# design.net
KiCad netlist of a schematic drawn in Altium Designer
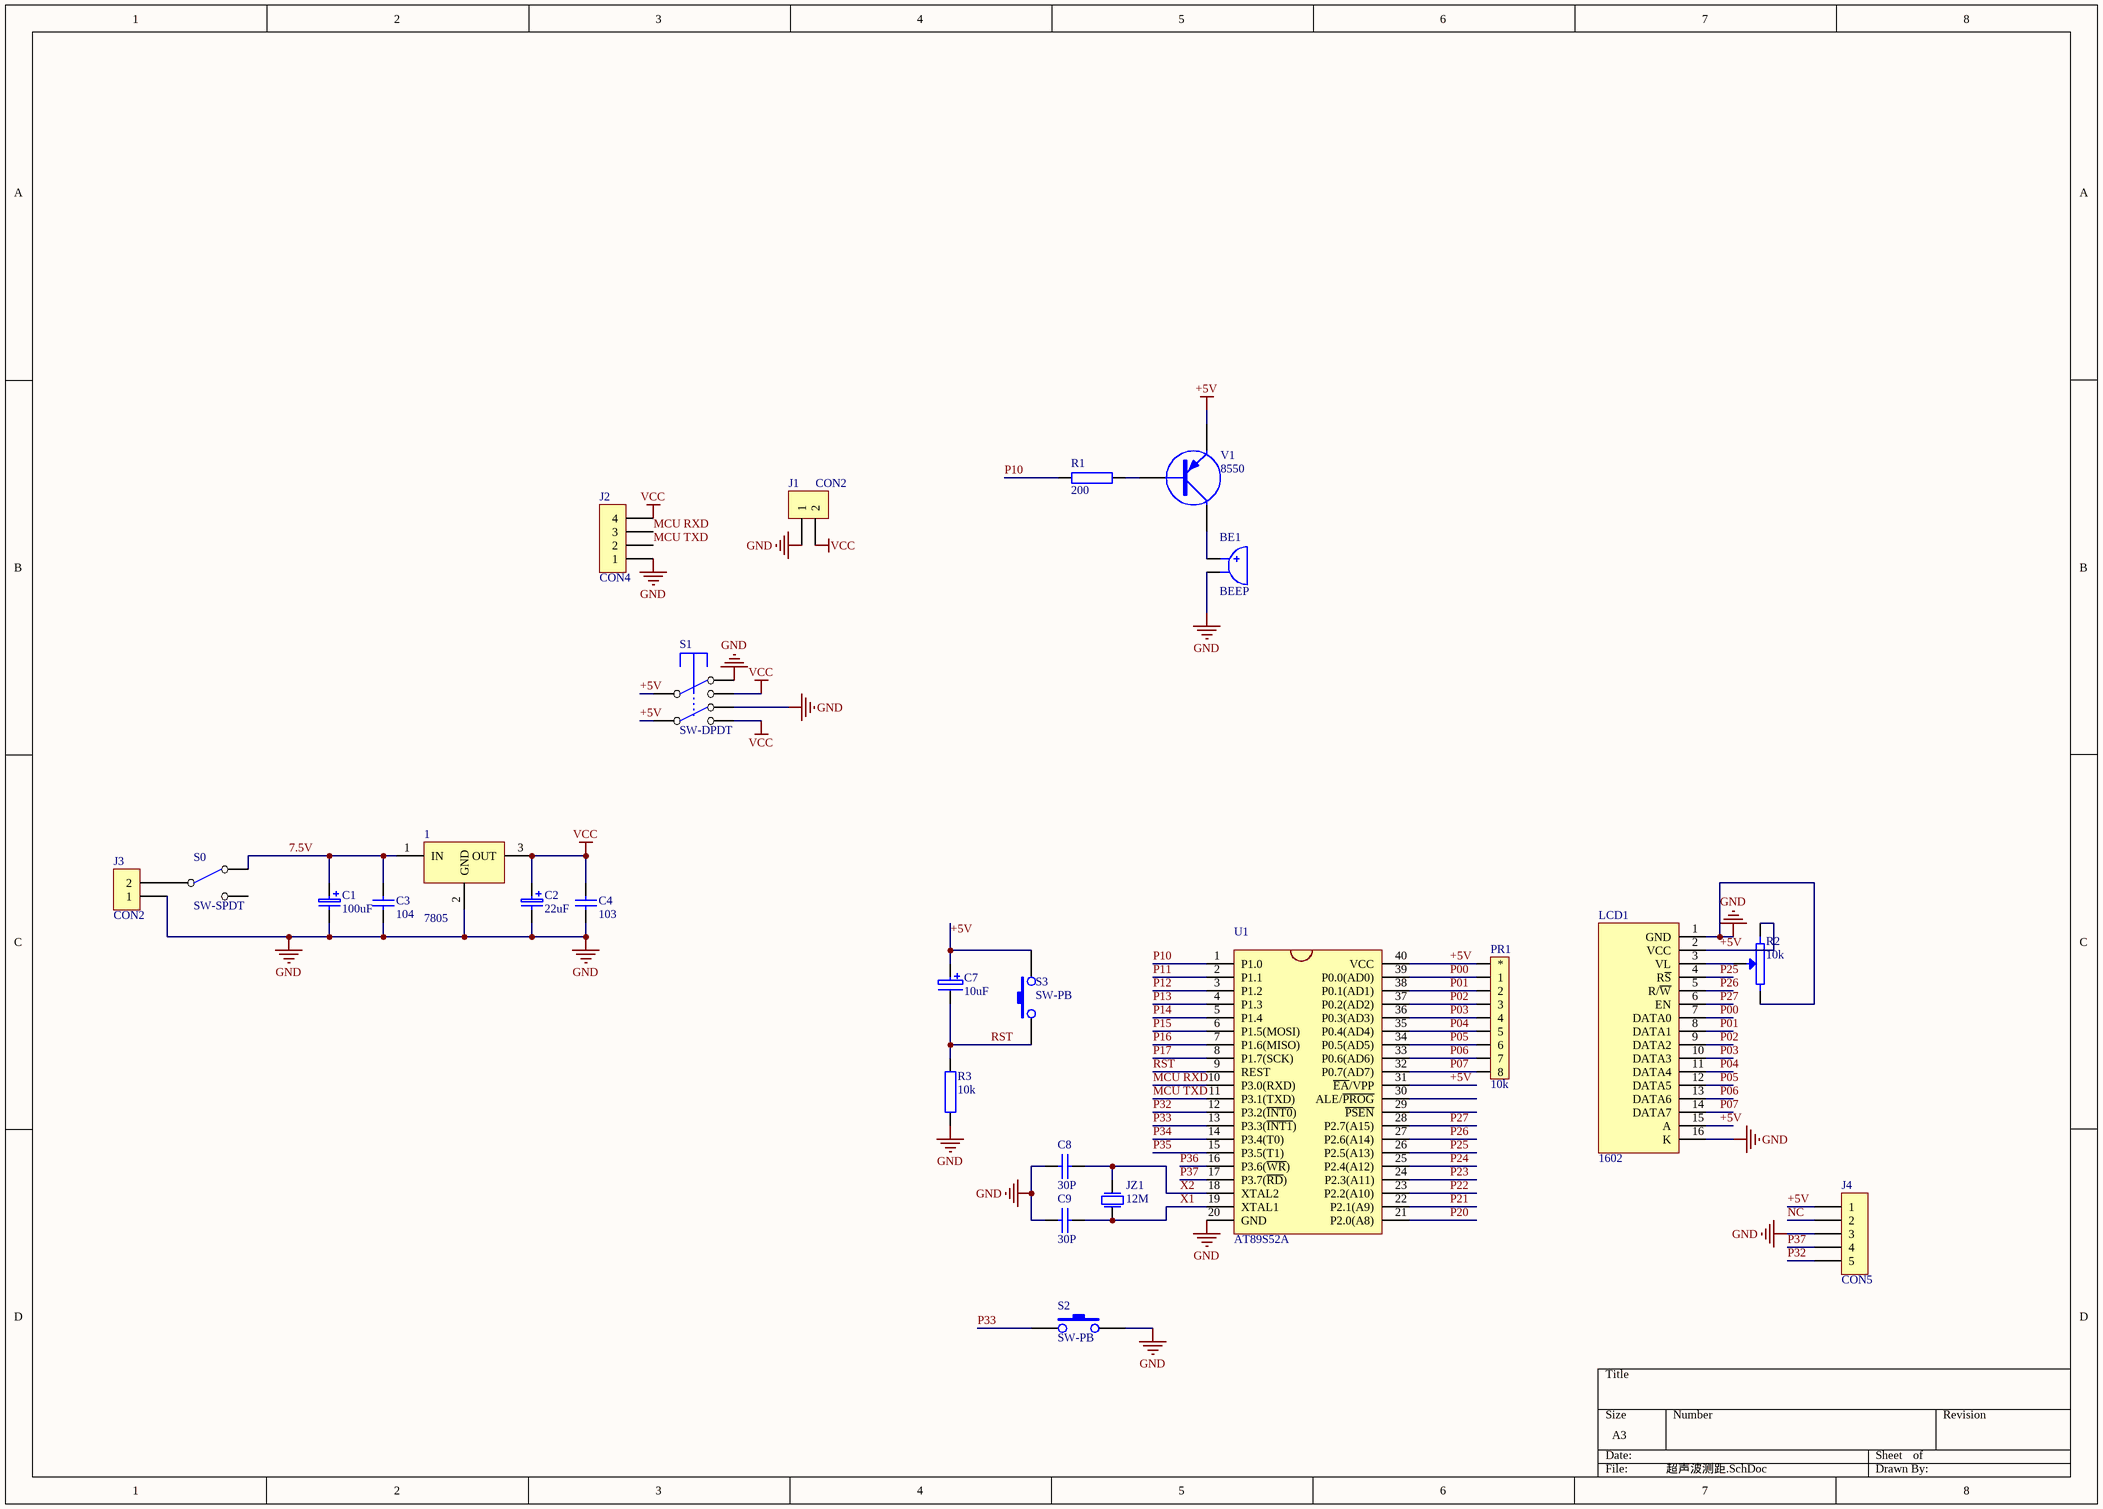
[diagram p0: 超声波测距.SchDoc]

(export (version "E")
  (design (tool "Eeschema 10.0.6"))
  (components
    (comp (ref "1") (value "7805") (footprint "TO-220") (libsource (lib "Voltage电压基准") (part "7805")))
    (comp (ref "BE1") (value "BEEP") (footprint "DB") (libsource (lib "Speaker扬声器") (part "BEEP")))
    (comp (ref "C1")
      (value "100uF")
      (footprint "CAO2")
      (description "Polarized Capacitor (Radial)")
      (fields (field (name "PUBLISHER") "Altium Limited"))
      (libsource (lib "Capacitance电容") (part "Cap Pol1"))
    )
    (comp (ref "C2")
      (value "22uF")
      (footprint "CAO1")
      (description "Polarized Capacitor (Radial)")
      (fields (field (name "PUBLISHER") "Altium Limited"))
      (libsource (lib "Capacitance电容") (part "Cap Pol1"))
    )
    (comp (ref "C3")
      (value "104")
      (footprint "CAP1")
      (description "Capacitor")
      (fields (field (name "PUBLISHER") "Altium Limited"))
      (libsource (lib "Capacitance电容") (part "Cap"))
    )
    (comp (ref "C4")
      (value "103")
      (footprint "CAP1")
      (description "Capacitor")
      (fields (field (name "PUBLISHER") "Altium Limited"))
      (libsource (lib "Capacitance电容") (part "Cap"))
    )
    (comp (ref "C7") (value "10uF") (footprint "CAO1") (libsource (lib "C电容") (part "CAP3")))
    (comp (ref "C8") (value "30P") (footprint "CAP1") (libsource (lib "C电容") (part "CAP1")))
    (comp (ref "C9") (value "30P") (footprint "CAP1") (libsource (lib "C电容") (part "CAP1")))
    (comp (ref "J1")
      (value "CON2")
      (footprint "sip-2")
      (description "Connector")
      (libsource (lib "") (part "CON2_1"))
    )
    (comp (ref "J2")
      (value "CON4")
      (footprint "sip-4")
      (description "Connector")
      (libsource (lib "接口") (part "CON4"))
    )
    (comp (ref "J3")
      (value "CON2")
      (footprint "sip-2")
      (description "Connector")
      (libsource (lib "接口") (part "CON2"))
    )
    (comp (ref "J4")
      (value "CON5")
      (footprint "sip-5")
      (description "Connector")
      (libsource (lib "接口") (part "CON5"))
    )
    (comp (ref "JZ1")
      (value "12M")
      (footprint "JZ1")
      (description "6.0000 8.000  11.0592  12.0000 24.000")
      (libsource (lib "J晶振") (part "CRY1"))
    )
    (comp (ref "LCD1") (value "1602") (footprint "RZ1602") (libsource (lib "LCD液晶") (part "1602")))
    (comp (ref "PR1") (value "10k") (footprint "RP1") (libsource (lib "R电阻") (part "PRES1")))
    (comp (ref "R1") (value "200") (footprint "AXIAL0.3") (libsource (lib "R电阻") (part "RES")))
    (comp (ref "R2")
      (value "10k")
      (footprint "RVR-5")
      (description "Potentiometer")
      (libsource (lib "R电阻") (part "RPOT-1"))
    )
    (comp (ref "R3") (value "10k") (footprint "AXIAL0.3") (libsource (lib "Resistance电阻") (part "RES")))
    (comp (ref "S0") (value "SW-SPDT") (footprint "SIP-3") (libsource (lib "SW开关") (part "SW-SPDT")))
    (comp (ref "S1") (value "SW-DPDT") (footprint "SW3") (libsource (lib "SW开关") (part "SW-DPDT")))
    (comp (ref "S2") (value "SW-PB") (footprint "SW6*6") (libsource (lib "SW开关") (part "SW-PB")))
    (comp (ref "S3") (value "SW-PB") (footprint "SW6*6") (libsource (lib "SW开关") (part "SW-PB")))
    (comp (ref "U1") (value "AT89S52A") (footprint "DIP-40") (libsource (lib "MCU") (part "AT89S52A")))
    (comp (ref "V1") (value "8550") (footprint "TO92a") (libsource (lib "Transistor三极管") (part "8550")))
  )
  (nets
    (net (code "1") (name "+5V") (class "Default")
      (node (ref "C7") (pin "1") (pintype "passive"))
      (node (ref "J4") (pin "1") (pinfunction "1_1") (pintype "passive"))
      (node (ref "LCD1") (pin "15") (pinfunction "A_15") (pintype "passive"))
      (node (ref "LCD1") (pin "2") (pinfunction "VCC_2") (pintype "passive"))
      (node (ref "PR1") (pin "1") (pinfunction "*_1") (pintype "passive"))
      (node (ref "R2") (pin "3") (pinfunction "3_3") (pintype "passive"))
      (node (ref "S1") (pin "2") (pinfunction "2_2") (pintype "passive"))
      (node (ref "S1") (pin "5") (pinfunction "5_5") (pintype "passive"))
      (node (ref "S3") (pin "2") (pinfunction "2_2") (pintype "passive"))
      (node (ref "U1") (pin "31") (pinfunction "~{EA}/VPP_31") (pintype "passive"))
      (node (ref "U1") (pin "40") (pinfunction "VCC_40") (pintype "passive"))
      (node (ref "V1") (pin "1") (pinfunction "E_1") (pintype "passive"))
    )
    (net (code "2") (name "/7.5V") (class "Default")
      (node (ref "1") (pin "1") (pinfunction "IN_1") (pintype "passive"))
      (node (ref "C1") (pin "1") (pinfunction "1_1") (pintype "passive"))
      (node (ref "C3") (pin "2") (pinfunction "2_2") (pintype "passive"))
      (node (ref "S0") (pin "1") (pinfunction "1_1") (pintype "passive"))
    )
    (net (code "3") (name "/MCU RXD") (class "Default")
      (node (ref "J2") (pin "3") (pinfunction "3_3") (pintype "passive"))
      (node (ref "U1") (pin "10") (pinfunction "P3.0(RXD)_10") (pintype "passive"))
    )
    (net (code "4") (name "/MCU TXD") (class "Default")
      (node (ref "J2") (pin "2") (pinfunction "2_2") (pintype "passive"))
      (node (ref "U1") (pin "11") (pinfunction "P3.1(TXD)_11") (pintype "passive"))
    )
    (net (code "5") (name "/NC") (class "Default")
      (node (ref "J4") (pin "2") (pinfunction "2_2") (pintype "passive"))
    )
    (net (code "6") (name "/P00") (class "Default")
      (node (ref "LCD1") (pin "7") (pinfunction "DATA0_7") (pintype "passive"))
      (node (ref "PR1") (pin "2") (pinfunction "1_2") (pintype "passive"))
      (node (ref "U1") (pin "39") (pinfunction "P0.0(AD0)_39") (pintype "passive"))
    )
    (net (code "7") (name "/P01") (class "Default")
      (node (ref "LCD1") (pin "8") (pinfunction "DATA1_8") (pintype "passive"))
      (node (ref "PR1") (pin "3") (pinfunction "2_3") (pintype "passive"))
      (node (ref "U1") (pin "38") (pinfunction "P0.1(AD1)_38") (pintype "passive"))
    )
    (net (code "8") (name "/P02") (class "Default")
      (node (ref "LCD1") (pin "9") (pinfunction "DATA2_9") (pintype "passive"))
      (node (ref "PR1") (pin "4") (pinfunction "3_4") (pintype "passive"))
      (node (ref "U1") (pin "37") (pinfunction "P0.2(AD2)_37") (pintype "passive"))
    )
    (net (code "9") (name "/P03") (class "Default")
      (node (ref "LCD1") (pin "10") (pinfunction "DATA3_10") (pintype "passive"))
      (node (ref "PR1") (pin "5") (pinfunction "4_5") (pintype "passive"))
      (node (ref "U1") (pin "36") (pinfunction "P0.3(AD3)_36") (pintype "passive"))
    )
    (net (code "10") (name "/P04") (class "Default")
      (node (ref "LCD1") (pin "11") (pinfunction "DATA4_11") (pintype "passive"))
      (node (ref "PR1") (pin "6") (pinfunction "5_6") (pintype "passive"))
      (node (ref "U1") (pin "35") (pinfunction "P0.4(AD4)_35") (pintype "passive"))
    )
    (net (code "11") (name "/P05") (class "Default")
      (node (ref "LCD1") (pin "12") (pinfunction "DATA5_12") (pintype "passive"))
      (node (ref "PR1") (pin "7") (pinfunction "6_7") (pintype "passive"))
      (node (ref "U1") (pin "34") (pinfunction "P0.5(AD5)_34") (pintype "passive"))
    )
    (net (code "12") (name "/P06") (class "Default")
      (node (ref "LCD1") (pin "13") (pinfunction "DATA6_13") (pintype "passive"))
      (node (ref "PR1") (pin "8") (pinfunction "7_8") (pintype "passive"))
      (node (ref "U1") (pin "33") (pinfunction "P0.6(AD6)_33") (pintype "passive"))
    )
    (net (code "13") (name "/P07") (class "Default")
      (node (ref "LCD1") (pin "14") (pinfunction "DATA7_14") (pintype "passive"))
      (node (ref "PR1") (pin "9") (pinfunction "8_9") (pintype "passive"))
      (node (ref "U1") (pin "32") (pinfunction "P0.7(AD7)_32") (pintype "passive"))
    )
    (net (code "14") (name "/P10") (class "Default")
      (node (ref "R1") (pin "1") (pinfunction "1_1") (pintype "passive"))
      (node (ref "U1") (pin "1") (pinfunction "P1.0_1") (pintype "passive"))
    )
    (net (code "15") (name "/P11") (class "Default")
      (node (ref "U1") (pin "2") (pinfunction "P1.1_2") (pintype "passive"))
    )
    (net (code "16") (name "/P12") (class "Default")
      (node (ref "U1") (pin "3") (pinfunction "P1.2_3") (pintype "passive"))
    )
    (net (code "17") (name "/P13") (class "Default")
      (node (ref "U1") (pin "4") (pinfunction "P1.3_4") (pintype "passive"))
    )
    (net (code "18") (name "/P14") (class "Default")
      (node (ref "U1") (pin "5") (pinfunction "P1.4_5") (pintype "passive"))
    )
    (net (code "19") (name "/P15") (class "Default")
      (node (ref "U1") (pin "6") (pinfunction "P1.5(MOSI)_6") (pintype "passive"))
    )
    (net (code "20") (name "/P16") (class "Default")
      (node (ref "U1") (pin "7") (pinfunction "P1.6(MISO)_7") (pintype "passive"))
    )
    (net (code "21") (name "/P17") (class "Default")
      (node (ref "U1") (pin "8") (pinfunction "P1.7(SCK)_8") (pintype "passive"))
    )
    (net (code "22") (name "/P20") (class "Default")
      (node (ref "U1") (pin "21") (pinfunction "P2.0(A8)_21") (pintype "passive"))
    )
    (net (code "23") (name "/P21") (class "Default")
      (node (ref "U1") (pin "22") (pinfunction "P2.1(A9)_22") (pintype "passive"))
    )
    (net (code "24") (name "/P22") (class "Default")
      (node (ref "U1") (pin "23") (pinfunction "P2.2(A10)_23") (pintype "passive"))
    )
    (net (code "25") (name "/P23") (class "Default")
      (node (ref "U1") (pin "24") (pinfunction "P2.3(A11)_24") (pintype "passive"))
    )
    (net (code "26") (name "/P24") (class "Default")
      (node (ref "U1") (pin "25") (pinfunction "P2.4(A12)_25") (pintype "passive"))
    )
    (net (code "27") (name "/P25") (class "Default")
      (node (ref "LCD1") (pin "4") (pinfunction "R~{S}_4") (pintype "passive"))
      (node (ref "U1") (pin "26") (pinfunction "P2.5(A13)_26") (pintype "passive"))
    )
    (net (code "28") (name "/P26") (class "Default")
      (node (ref "LCD1") (pin "5") (pinfunction "R/~{W}_5") (pintype "passive"))
      (node (ref "U1") (pin "27") (pinfunction "P2.6(A14)_27") (pintype "passive"))
    )
    (net (code "29") (name "/P27") (class "Default")
      (node (ref "LCD1") (pin "6") (pinfunction "EN_6") (pintype "passive"))
      (node (ref "U1") (pin "28") (pinfunction "P2.7(A15)_28") (pintype "passive"))
    )
    (net (code "30") (name "/P32") (class "Default")
      (node (ref "J4") (pin "5") (pinfunction "5_5") (pintype "passive"))
      (node (ref "U1") (pin "12") (pinfunction "P3.2(~{INT0})_12") (pintype "passive"))
    )
    (net (code "31") (name "/P33") (class "Default")
      (node (ref "S2") (pin "1") (pinfunction "1_1") (pintype "passive"))
      (node (ref "U1") (pin "13") (pinfunction "P3.3(~{INT1})_13") (pintype "passive"))
    )
    (net (code "32") (name "/P34") (class "Default")
      (node (ref "U1") (pin "14") (pinfunction "P3.4(T0)_14") (pintype "passive"))
    )
    (net (code "33") (name "/P35") (class "Default")
      (node (ref "U1") (pin "15") (pinfunction "P3.5(T1)_15") (pintype "passive"))
    )
    (net (code "34") (name "/P36") (class "Default")
      (node (ref "U1") (pin "16") (pinfunction "P3.6(~{WR})_16") (pintype "passive"))
    )
    (net (code "35") (name "/P37") (class "Default")
      (node (ref "J4") (pin "4") (pinfunction "4_4") (pintype "passive"))
      (node (ref "U1") (pin "17") (pinfunction "P3.7(~{RD})_17") (pintype "passive"))
    )
    (net (code "36") (name "/RST") (class "Default")
      (node (ref "C7") (pin "2") (pintype "passive"))
      (node (ref "R3") (pin "2") (pinfunction "2_2") (pintype "passive"))
      (node (ref "S3") (pin "1") (pinfunction "1_1") (pintype "passive"))
      (node (ref "U1") (pin "9") (pinfunction "REST_9") (pintype "passive"))
    )
    (net (code "37") (name "/X1") (class "Default")
      (node (ref "C9") (pin "1") (pinfunction "1_1") (pintype "passive"))
      (node (ref "JZ1") (pin "2") (pinfunction "P2_2") (pintype "passive"))
      (node (ref "U1") (pin "19") (pinfunction "XTAL1_19") (pintype "passive"))
    )
    (net (code "38") (name "/X2") (class "Default")
      (node (ref "C8") (pin "1") (pinfunction "1_1") (pintype "passive"))
      (node (ref "JZ1") (pin "1") (pinfunction "P1_1") (pintype "passive"))
      (node (ref "U1") (pin "18") (pinfunction "XTAL2_18") (pintype "passive"))
    )
    (net (code "39") (name "GND") (class "Default")
      (node (ref "1") (pin "2") (pinfunction "GND_2") (pintype "passive"))
      (node (ref "BE1") (pin "2") (pinfunction "-_2") (pintype "passive"))
      (node (ref "C1") (pin "2") (pinfunction "2_2") (pintype "passive"))
      (node (ref "C2") (pin "2") (pinfunction "2_2") (pintype "passive"))
      (node (ref "C3") (pin "1") (pinfunction "1_1") (pintype "passive"))
      (node (ref "C4") (pin "1") (pinfunction "1_1") (pintype "passive"))
      (node (ref "C8") (pin "2") (pinfunction "2_2") (pintype "passive"))
      (node (ref "C9") (pin "2") (pinfunction "2_2") (pintype "passive"))
      (node (ref "J1") (pin "1") (pinfunction "1_1") (pintype "passive"))
      (node (ref "J2") (pin "1") (pinfunction "1_1") (pintype "passive"))
      (node (ref "J3") (pin "1") (pinfunction "1_1") (pintype "passive"))
      (node (ref "J4") (pin "3") (pinfunction "3_3") (pintype "passive"))
      (node (ref "LCD1") (pin "1") (pinfunction "GND_1") (pintype "passive"))
      (node (ref "LCD1") (pin "16") (pinfunction "K_16") (pintype "passive"))
      (node (ref "R2") (pin "1") (pinfunction "1_1") (pintype "passive"))
      (node (ref "R3") (pin "1") (pinfunction "1_1") (pintype "passive"))
      (node (ref "S1") (pin "0") (pinfunction "0_0") (pintype "passive"))
      (node (ref "S1") (pin "3") (pinfunction "3_3") (pintype "passive"))
      (node (ref "S2") (pin "2") (pinfunction "2_2") (pintype "passive"))
      (node (ref "U1") (pin "20") (pinfunction "GND_20") (pintype "passive"))
    )
    (net (code "40") (name "Net-(BE1-+)") (class "Default")
      (node (ref "BE1") (pin "1") (pinfunction "+_1") (pintype "passive"))
      (node (ref "V1") (pin "3") (pinfunction "C_3") (pintype "passive"))
    )
    (net (code "41") (name "Net-(LCD1-VL)") (class "Default")
      (node (ref "LCD1") (pin "3") (pinfunction "VL_3") (pintype "passive"))
      (node (ref "R2") (pin "2") (pinfunction "W_2") (pintype "passive"))
    )
    (net (code "42") (name "Net-(S0-c)") (class "Default")
      (node (ref "J3") (pin "2") (pinfunction "2_2") (pintype "passive"))
      (node (ref "S0") (pin "2") (pinfunction "c_2") (pintype "passive"))
    )
    (net (code "43") (name "Net-(V1-B)") (class "Default")
      (node (ref "R1") (pin "2") (pinfunction "2_2") (pintype "passive"))
      (node (ref "V1") (pin "2") (pinfunction "B_2") (pintype "passive"))
    )
    (net (code "44") (name "VCC") (class "Default")
      (node (ref "1") (pin "3") (pinfunction "OUT_3") (pintype "passive"))
      (node (ref "C2") (pin "1") (pinfunction "1_1") (pintype "passive"))
      (node (ref "C4") (pin "2") (pinfunction "2_2") (pintype "passive"))
      (node (ref "J1") (pin "2") (pinfunction "2_2") (pintype "passive"))
      (node (ref "J2") (pin "4") (pinfunction "4_4") (pintype "passive"))
      (node (ref "S1") (pin "1") (pinfunction "1_1") (pintype "passive"))
      (node (ref "S1") (pin "4") (pinfunction "4_4") (pintype "passive"))
    )
    (net (code "45") (name "unconnected-(S0-Pad3)") (class "Default")
      (node (ref "S0") (pin "3") (pinfunction "3_3") (pintype "passive"))
    )
    (net (code "46") (name "unconnected-(U1-ALE{slash}~{PROG}-Pad30)") (class "Default")
      (node (ref "U1") (pin "30") (pinfunction "ALE/~{PROG}_30") (pintype "passive"))
    )
    (net (code "47") (name "unconnected-(U1-~{PSEN}-Pad29)") (class "Default")
      (node (ref "U1") (pin "29") (pinfunction "~{PSEN}_29") (pintype "passive"))
    )
  )
)
